# astable_sch_1.net
KiCad netlist of a schematic drawn in EAGLE
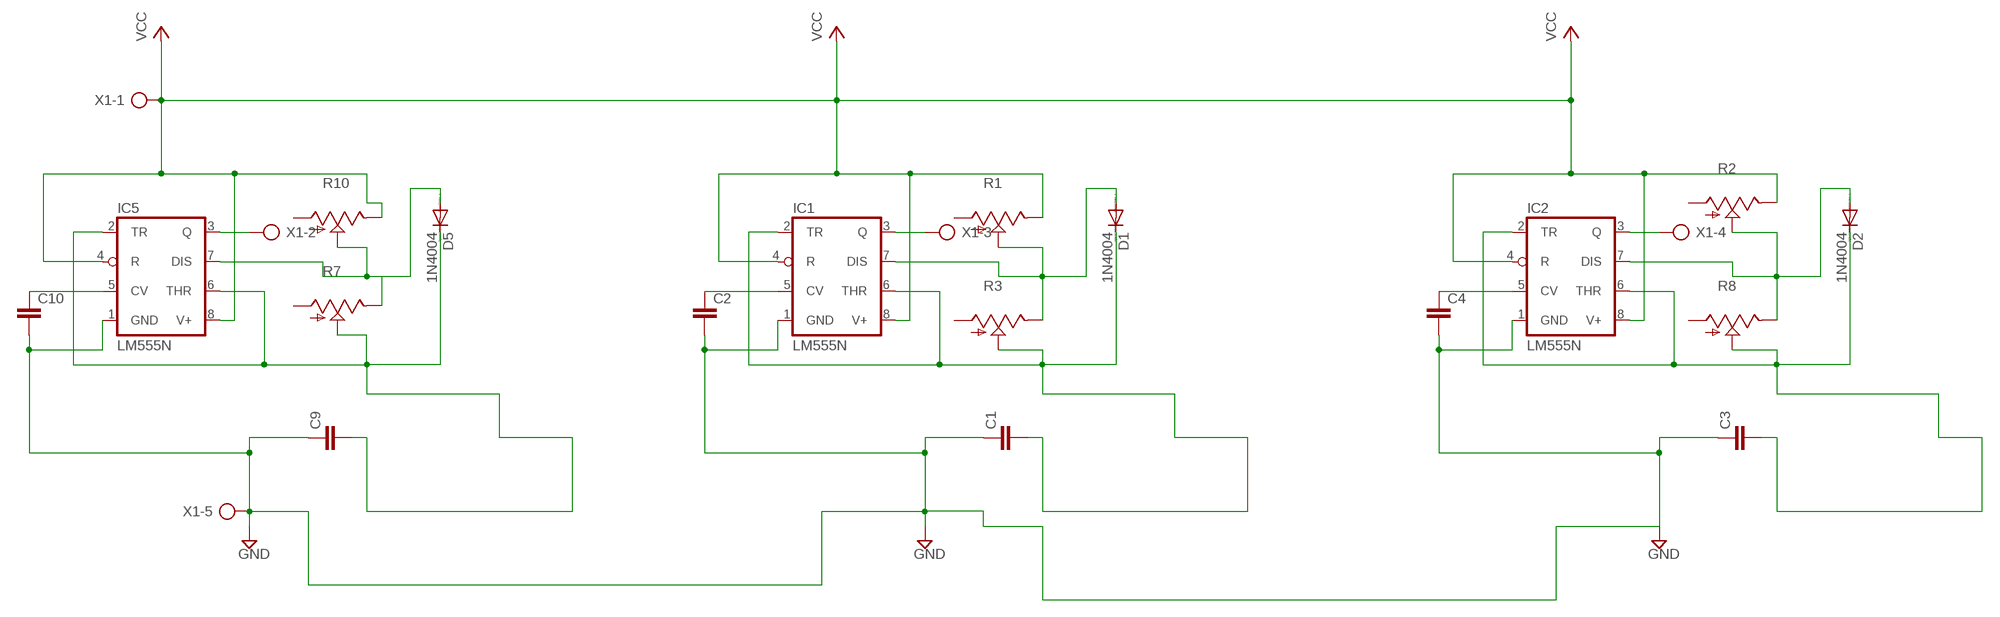
[diagram p0: schematic, sheet 1]

(export (version "E")
  (design (tool "Eeschema 10.0.6"))
  (components
    (comp (ref "C1")
      (value "C-EU025-024X044")
      (footprint "eagle-import:C025-024X044")
      (libsource (lib "eagle-import") (part "C-EU025-024X044"))
    )
    (comp (ref "C2")
      (value "C-EU025-024X044")
      (footprint "eagle-import:C025-024X044")
      (libsource (lib "eagle-import") (part "C-EU025-024X044"))
    )
    (comp (ref "C3")
      (value "C-EU025-024X044")
      (footprint "eagle-import:C025-024X044")
      (libsource (lib "eagle-import") (part "C-EU025-024X044"))
    )
    (comp (ref "C4")
      (value "C-EU025-024X044")
      (footprint "eagle-import:C025-024X044")
      (libsource (lib "eagle-import") (part "C-EU025-024X044"))
    )
    (comp (ref "C9")
      (value "C-EU025-024X044")
      (footprint "eagle-import:C025-024X044")
      (libsource (lib "eagle-import") (part "C-EU025-024X044"))
    )
    (comp (ref "C10")
      (value "C-EU025-024X044")
      (footprint "eagle-import:C025-024X044")
      (libsource (lib "eagle-import") (part "C-EU025-024X044"))
    )
    (comp (ref "D1")
      (value "1N4004")
      (footprint "eagle-import:DO41-10")
      (libsource (lib "eagle-import") (part "1N4004"))
    )
    (comp (ref "D2")
      (value "1N4004")
      (footprint "eagle-import:DO41-10")
      (libsource (lib "eagle-import") (part "1N4004"))
    )
    (comp (ref "D5")
      (value "1N4004")
      (footprint "eagle-import:DO41-10")
      (libsource (lib "eagle-import") (part "1N4004"))
    )
    (comp (ref "IC1")
      (value "LM555N")
      (footprint "eagle-import:DIL08")
      (libsource (lib "eagle-import") (part "555NLM"))
    )
    (comp (ref "IC2")
      (value "LM555N")
      (footprint "eagle-import:DIL08")
      (libsource (lib "eagle-import") (part "555NLM"))
    )
    (comp (ref "IC5")
      (value "LM555N")
      (footprint "eagle-import:DIL08")
      (libsource (lib "eagle-import") (part "555NLM"))
    )
    (comp (ref "R1")
      (value "TRIM_US-B25V")
      (footprint "eagle-import:B25V")
      (libsource (lib "eagle-import") (part "TRIM_US-B25V"))
    )
    (comp (ref "R2")
      (value "TRIM_US-B25V")
      (footprint "eagle-import:B25V")
      (libsource (lib "eagle-import") (part "TRIM_US-B25V"))
    )
    (comp (ref "R3")
      (value "TRIM_US-B25V")
      (footprint "eagle-import:B25V")
      (libsource (lib "eagle-import") (part "TRIM_US-B25V"))
    )
    (comp (ref "R7")
      (value "TRIM_US-B25V")
      (footprint "eagle-import:B25V")
      (libsource (lib "eagle-import") (part "TRIM_US-B25V"))
    )
    (comp (ref "R8")
      (value "TRIM_US-B25V")
      (footprint "eagle-import:B25V")
      (libsource (lib "eagle-import") (part "TRIM_US-B25V"))
    )
    (comp (ref "R10")
      (value "TRIM_US-B25V")
      (footprint "eagle-import:B25V")
      (libsource (lib "eagle-import") (part "TRIM_US-B25V"))
    )
    (comp (ref "X1")
      (value "AK300/5")
      (footprint "eagle-import:AK300_5")
      (libsource (lib "eagle-import") (part "AK300/5"))
    )
  )
  (nets
    (net (code "1") (name "GND") (class "Default")
      (node (ref "C1") (pin "1") (pinfunction "1_1") (pintype "passive"))
      (node (ref "C10") (pin "2") (pinfunction "2_2") (pintype "passive"))
      (node (ref "C2") (pin "2") (pinfunction "2_2") (pintype "passive"))
      (node (ref "C3") (pin "1") (pinfunction "1_1") (pintype "passive"))
      (node (ref "C4") (pin "2") (pinfunction "2_2") (pintype "passive"))
      (node (ref "C9") (pin "1") (pinfunction "1_1") (pintype "passive"))
      (node (ref "IC1") (pin "1") (pinfunction "GND_1") (pintype "power_in"))
      (node (ref "IC2") (pin "1") (pinfunction "GND_1") (pintype "power_in"))
      (node (ref "IC5") (pin "1") (pinfunction "GND_1") (pintype "power_in"))
      (node (ref "X1") (pin "5") (pinfunction "KL_5") (pintype "passive"))
    )
    (net (code "2") (name "Net-(IC1-CV)") (class "Default")
      (node (ref "C2") (pin "1") (pinfunction "1_1") (pintype "passive"))
      (node (ref "IC1") (pin "5") (pinfunction "CV_5") (pintype "input"))
    )
    (net (code "3") (name "Net-(IC1-DIS)") (class "Default")
      (node (ref "D1") (pin "A") (pinfunction "A_A") (pintype "passive"))
      (node (ref "IC1") (pin "7") (pinfunction "DIS_7") (pintype "input"))
      (node (ref "R1") (pin "S") (pinfunction "S_S") (pintype "passive"))
      (node (ref "R3") (pin "E") (pinfunction "E_E") (pintype "passive"))
    )
    (net (code "4") (name "Net-(IC1-Q)") (class "Default")
      (node (ref "IC1") (pin "3") (pinfunction "Q_3") (pintype "output"))
      (node (ref "X1") (pin "3") (pinfunction "KL_3") (pintype "passive"))
    )
    (net (code "5") (name "Net-(IC1-THR)") (class "Default")
      (node (ref "C1") (pin "2") (pinfunction "2_2") (pintype "passive"))
      (node (ref "D1") (pin "C") (pinfunction "C_C") (pintype "passive"))
      (node (ref "IC1") (pin "2") (pinfunction "TR_2") (pintype "input"))
      (node (ref "IC1") (pin "6") (pinfunction "THR_6") (pintype "input"))
      (node (ref "R3") (pin "S") (pinfunction "S_S") (pintype "passive"))
    )
    (net (code "6") (name "Net-(IC2-CV)") (class "Default")
      (node (ref "C4") (pin "1") (pinfunction "1_1") (pintype "passive"))
      (node (ref "IC2") (pin "5") (pinfunction "CV_5") (pintype "input"))
    )
    (net (code "7") (name "Net-(IC2-DIS)") (class "Default")
      (node (ref "D2") (pin "A") (pinfunction "A_A") (pintype "passive"))
      (node (ref "IC2") (pin "7") (pinfunction "DIS_7") (pintype "input"))
      (node (ref "R2") (pin "S") (pinfunction "S_S") (pintype "passive"))
      (node (ref "R8") (pin "E") (pinfunction "E_E") (pintype "passive"))
    )
    (net (code "8") (name "Net-(IC2-Q)") (class "Default")
      (node (ref "IC2") (pin "3") (pinfunction "Q_3") (pintype "output"))
      (node (ref "X1") (pin "4") (pinfunction "KL_4") (pintype "passive"))
    )
    (net (code "9") (name "Net-(IC2-THR)") (class "Default")
      (node (ref "C3") (pin "2") (pinfunction "2_2") (pintype "passive"))
      (node (ref "D2") (pin "C") (pinfunction "C_C") (pintype "passive"))
      (node (ref "IC2") (pin "2") (pinfunction "TR_2") (pintype "input"))
      (node (ref "IC2") (pin "6") (pinfunction "THR_6") (pintype "input"))
      (node (ref "R8") (pin "S") (pinfunction "S_S") (pintype "passive"))
    )
    (net (code "10") (name "Net-(IC5-CV)") (class "Default")
      (node (ref "C10") (pin "1") (pinfunction "1_1") (pintype "passive"))
      (node (ref "IC5") (pin "5") (pinfunction "CV_5") (pintype "input"))
    )
    (net (code "11") (name "Net-(IC5-DIS)") (class "Default")
      (node (ref "D5") (pin "A") (pinfunction "A_A") (pintype "passive"))
      (node (ref "IC5") (pin "7") (pinfunction "DIS_7") (pintype "input"))
      (node (ref "R10") (pin "S") (pinfunction "S_S") (pintype "passive"))
      (node (ref "R7") (pin "E") (pinfunction "E_E") (pintype "passive"))
    )
    (net (code "12") (name "Net-(IC5-Q)") (class "Default")
      (node (ref "IC5") (pin "3") (pinfunction "Q_3") (pintype "output"))
      (node (ref "X1") (pin "2") (pinfunction "KL_2") (pintype "passive"))
    )
    (net (code "13") (name "Net-(IC5-THR)") (class "Default")
      (node (ref "C9") (pin "2") (pinfunction "2_2") (pintype "passive"))
      (node (ref "D5") (pin "C") (pinfunction "C_C") (pintype "passive"))
      (node (ref "IC5") (pin "2") (pinfunction "TR_2") (pintype "input"))
      (node (ref "IC5") (pin "6") (pinfunction "THR_6") (pintype "input"))
      (node (ref "R7") (pin "S") (pinfunction "S_S") (pintype "passive"))
    )
    (net (code "14") (name "VCC") (class "Default")
      (node (ref "IC1") (pin "4") (pinfunction "R_4") (pintype "input"))
      (node (ref "IC1") (pin "8") (pinfunction "V+_8") (pintype "power_in"))
      (node (ref "IC2") (pin "4") (pinfunction "R_4") (pintype "input"))
      (node (ref "IC2") (pin "8") (pinfunction "V+_8") (pintype "power_in"))
      (node (ref "IC5") (pin "4") (pinfunction "R_4") (pintype "input"))
      (node (ref "IC5") (pin "8") (pinfunction "V+_8") (pintype "power_in"))
      (node (ref "R1") (pin "E") (pinfunction "E_E") (pintype "passive"))
      (node (ref "R10") (pin "E") (pinfunction "E_E") (pintype "passive"))
      (node (ref "R2") (pin "E") (pinfunction "E_E") (pintype "passive"))
      (node (ref "X1") (pin "1") (pinfunction "KL_1") (pintype "passive"))
    )
    (net (code "15") (name "unconnected-(R1-PadA)") (class "Default")
      (node (ref "R1") (pin "A") (pinfunction "A_A") (pintype "passive"))
    )
    (net (code "16") (name "unconnected-(R2-PadA)") (class "Default")
      (node (ref "R2") (pin "A") (pinfunction "A_A") (pintype "passive"))
    )
    (net (code "17") (name "unconnected-(R3-PadA)") (class "Default")
      (node (ref "R3") (pin "A") (pinfunction "A_A") (pintype "passive"))
    )
    (net (code "18") (name "unconnected-(R7-PadA)") (class "Default")
      (node (ref "R7") (pin "A") (pinfunction "A_A") (pintype "passive"))
    )
    (net (code "19") (name "unconnected-(R8-PadA)") (class "Default")
      (node (ref "R8") (pin "A") (pinfunction "A_A") (pintype "passive"))
    )
    (net (code "20") (name "unconnected-(R10-PadA)") (class "Default")
      (node (ref "R10") (pin "A") (pinfunction "A_A") (pintype "passive"))
    )
  )
)
